# Arm_control_pull.net
KiCad netlist of a schematic drawn in Altium Designer
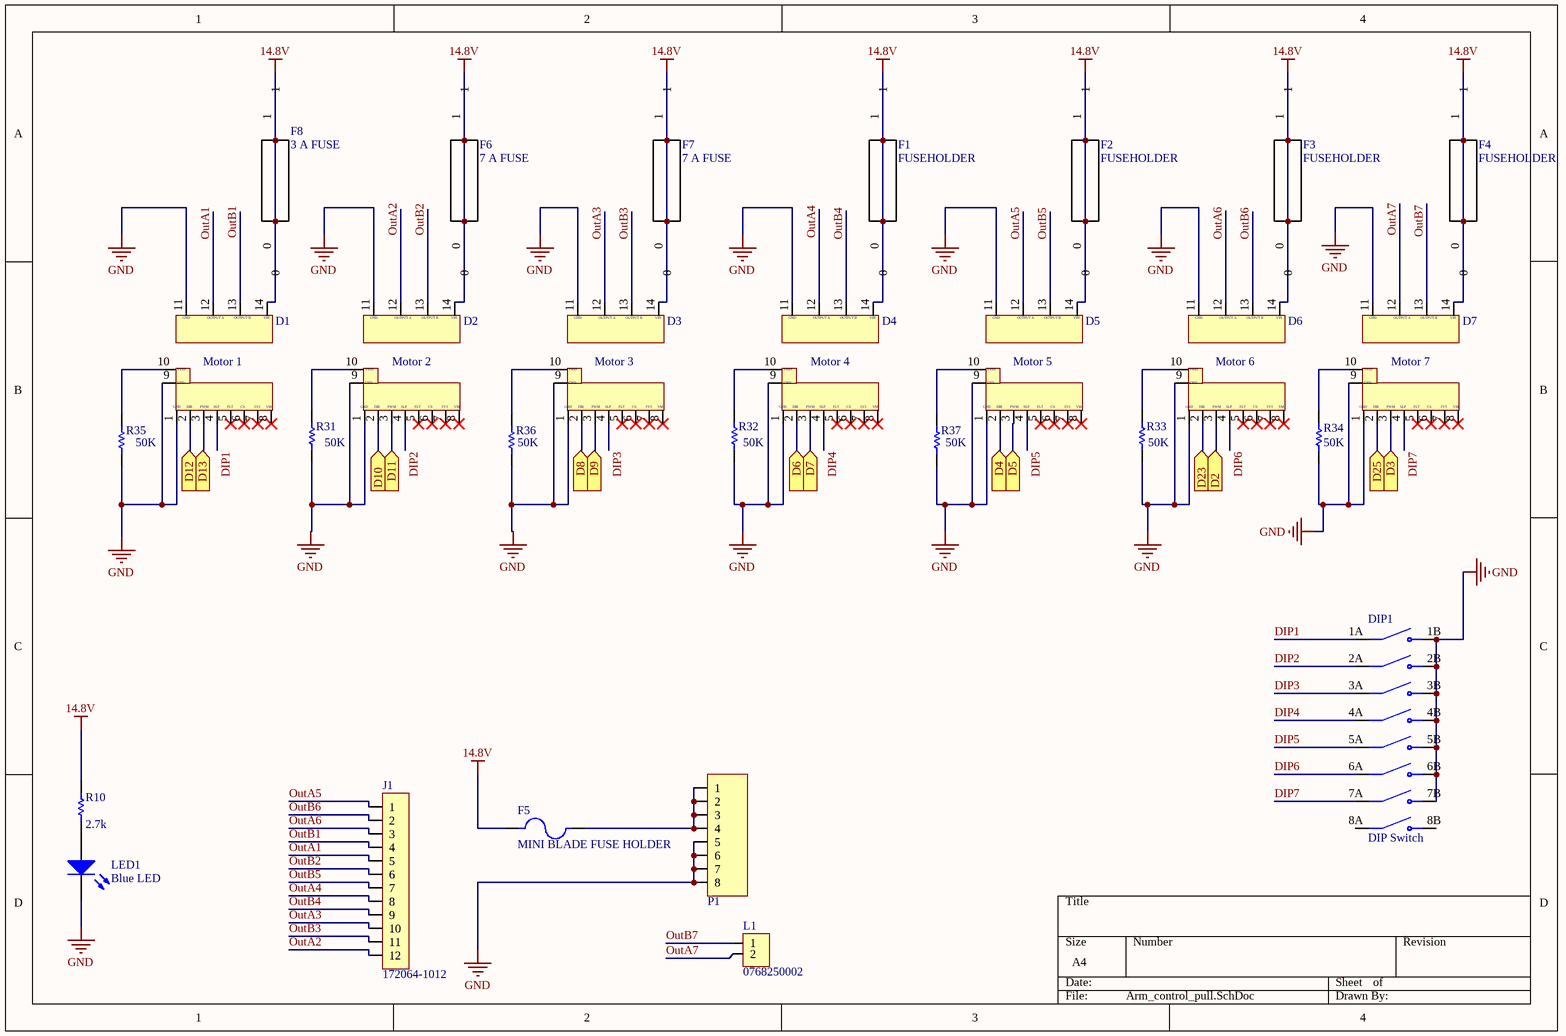
[diagram p0: Arm_control_pull.SchDoc]

(export (version "E")
  (design (tool "Eeschema 10.0.6"))
  (components
    (comp (ref "D1")
      (value "Pololu G2 High-Power Motor Driver 18v25")
      (footprint "POLOLU 18V25")
      (libsource (lib "RSX_Modules") (part "Pololu G2 High-Power Motor Driver 18v25"))
    )
    (comp (ref "D2")
      (value "Pololu G2 High-Power Motor Driver 18v25")
      (footprint "POLOLU 18V25")
      (libsource (lib "RSX_Modules") (part "Pololu G2 High-Power Motor Driver 18v25"))
    )
    (comp (ref "D3")
      (value "Pololu G2 High-Power Motor Driver 18v25")
      (footprint "POLOLU 18V25")
      (libsource (lib "RSX_Modules") (part "Pololu G2 High-Power Motor Driver 18v25"))
    )
    (comp (ref "D4")
      (value "Pololu G2 High-Power Motor Driver 18v25")
      (footprint "POLOLU 18V25")
      (libsource (lib "RSX_Modules") (part "Pololu G2 High-Power Motor Driver 18v25"))
    )
    (comp (ref "D5")
      (value "Pololu G2 High-Power Motor Driver 18v25")
      (footprint "POLOLU 18V25")
      (libsource (lib "RSX_Modules") (part "Pololu G2 High-Power Motor Driver 18v25"))
    )
    (comp (ref "D6")
      (value "Pololu G2 High-Power Motor Driver 18v25")
      (footprint "POLOLU 18V25")
      (libsource (lib "RSX_Modules") (part "Pololu G2 High-Power Motor Driver 18v25"))
    )
    (comp (ref "D7")
      (value "Pololu G2 High-Power Motor Driver 18v25")
      (footprint "POLOLU 18V25")
      (libsource (lib "RSX_Modules") (part "Pololu G2 High-Power Motor Driver 18v25"))
    )
    (comp (ref "DIP1")
      (value "DIP Switch")
      (footprint "DIP Switch")
      (libsource (lib "RSX_Modules") (part "DIP Switch"))
    )
    (comp (ref "F1")
      (value "FUSEHOLDER")
      (footprint "FUSEHOLDER 3557-20")
      (libsource (lib "RSX_Fuses") (part "FUSEHOLDER"))
    )
    (comp (ref "F2")
      (value "FUSEHOLDER")
      (footprint "FUSEHOLDER 3557-20")
      (libsource (lib "RSX_Fuses") (part "FUSEHOLDER"))
    )
    (comp (ref "F3")
      (value "FUSEHOLDER")
      (footprint "FUSEHOLDER 3557-20")
      (libsource (lib "RSX_Fuses") (part "FUSEHOLDER"))
    )
    (comp (ref "F4")
      (value "FUSEHOLDER")
      (footprint "FUSEHOLDER 3557-20")
      (libsource (lib "RSX_Fuses") (part "FUSEHOLDER"))
    )
    (comp (ref "F5")
      (value "MINI BLADE FUSE HOLDER")
      (footprint "RSX_Fuses:MINI FUSE HOLDER")
      (description "Fuse Holder 15A 32V 1 Circuit Blade Through Hole")
      (fields (field (name "MP") "01530007Z"))
      (libsource (lib "RSX_Fuses") (part "01530007Z"))
    )
    (comp (ref "F6")
      (value "7 A FUSE")
      (footprint "7 A FUSE  0407007.WR")
      (libsource (lib "RSX_Fuses") (part "7 A FUSE"))
    )
    (comp (ref "F7")
      (value "7 A FUSE")
      (footprint "7 A FUSE  0407007.WR")
      (libsource (lib "RSX_Fuses") (part "7 A FUSE"))
    )
    (comp (ref "F8")
      (value "3 A FUSE")
      (footprint "3A FUSE ERB-RG3R00V")
      (libsource (lib "RSX_Fuses") (part "3 A FUSE"))
    )
    (comp (ref "J1")
      (value "172064-1012")
      (footprint "172064-1012")
      (description "Conn Shrouded Header HDR 12 POS 5.7mm Solder RA Thru-Hole Tray")
      (libsource (lib "RSX_Connectors") (part "172064-1012"))
    )
    (comp (ref "L1")
      (value "0768250002")
      (footprint "MOLEX 0768250002")
      (description "Conn Power HDR 2 POS 5.7mm Solder RA Thru-Hole 2 Terminal 1 Port")
      (libsource (lib "RSX_Connectors") (part "0768250002"))
    )
    (comp (ref "LED1")
      (value "Blue LED")
      (footprint "LTST-C171TBKT")
      (libsource (lib "RSX_Diodes") (part "Blue LED"))
    )
    (comp (ref "P1")
      (value "Mini-Fit Jr 8 Pos RA")
      (footprint "MOLEX 172065-0208")
      (libsource (lib "RSX_Connectors") (part "Molex Mega-Fit 8pos Vert"))
    )
    (comp (ref "R10")
      (value "2.7k")
      (footprint "RESC1608X06N_0603")
      (description "Resistor")
      (fields (field (name "Comment") "Res1") (field (name "PUBLISHER") "Altium Limited"))
      (libsource (lib "RSX_Resistors") (part "Res1"))
    )
    (comp (ref "R31")
      (value "50K")
      (footprint "RESC1608X06N_0603")
      (description "Resistor")
      (fields (field (name "Comment") "Res1") (field (name "PUBLISHER") "Altium Limited"))
      (libsource (lib "RSX_Resistors") (part "Res1"))
    )
    (comp (ref "R32")
      (value "50K")
      (footprint "RESC1608X06N_0603")
      (description "Resistor")
      (fields (field (name "Comment") "Res1") (field (name "PUBLISHER") "Altium Limited"))
      (libsource (lib "RSX_Resistors") (part "Res1"))
    )
    (comp (ref "R33")
      (value "50K")
      (footprint "RESC1608X06N_0603")
      (description "Resistor")
      (fields (field (name "Comment") "Res1") (field (name "PUBLISHER") "Altium Limited"))
      (libsource (lib "RSX_Resistors") (part "Res1"))
    )
    (comp (ref "R34")
      (value "50K")
      (footprint "RESC1608X06N_0603")
      (description "Resistor")
      (fields (field (name "Comment") "Res1") (field (name "PUBLISHER") "Altium Limited"))
      (libsource (lib "RSX_Resistors") (part "Res1"))
    )
    (comp (ref "R35")
      (value "50K")
      (footprint "RESC1608X06N_0603")
      (description "Resistor")
      (fields (field (name "Comment") "Res1") (field (name "PUBLISHER") "Altium Limited"))
      (libsource (lib "RSX_Resistors") (part "Res1"))
    )
    (comp (ref "R36")
      (value "50K")
      (footprint "RESC1608X06N_0603")
      (description "Resistor")
      (fields (field (name "Comment") "Res1") (field (name "PUBLISHER") "Altium Limited"))
      (libsource (lib "RSX_Resistors") (part "Res1"))
    )
    (comp (ref "R37")
      (value "50K")
      (footprint "RESC1608X06N_0603")
      (description "Resistor")
      (fields (field (name "Comment") "Res1") (field (name "PUBLISHER") "Altium Limited"))
      (libsource (lib "RSX_Resistors") (part "Res1"))
    )
  )
  (nets
    (net (code "2") (name "/D2") (class "Default")
      (node (ref "D6") (pin "3") (pinfunction "3_3") (pintype "passive"))
    )
    (net (code "3") (name "/D3") (class "Default")
      (node (ref "D7") (pin "3") (pinfunction "3_3") (pintype "passive"))
    )
    (net (code "4") (name "/D4") (class "Default")
      (node (ref "D5") (pin "2") (pinfunction "2_2") (pintype "passive"))
    )
    (net (code "5") (name "/D5") (class "Default")
      (node (ref "D5") (pin "3") (pinfunction "3_3") (pintype "passive"))
    )
    (net (code "6") (name "/D6") (class "Default")
      (node (ref "D4") (pin "2") (pinfunction "2_2") (pintype "passive"))
    )
    (net (code "7") (name "/D7") (class "Default")
      (node (ref "D4") (pin "3") (pinfunction "3_3") (pintype "passive"))
    )
    (net (code "8") (name "/D8") (class "Default")
      (node (ref "D3") (pin "2") (pinfunction "2_2") (pintype "passive"))
    )
    (net (code "9") (name "/D9") (class "Default")
      (node (ref "D3") (pin "3") (pinfunction "3_3") (pintype "passive"))
    )
    (net (code "10") (name "/D10") (class "Default")
      (node (ref "D2") (pin "2") (pinfunction "2_2") (pintype "passive"))
    )
    (net (code "11") (name "/D11") (class "Default")
      (node (ref "D2") (pin "3") (pinfunction "3_3") (pintype "passive"))
    )
    (net (code "12") (name "/D12") (class "Default")
      (node (ref "D1") (pin "2") (pinfunction "2_2") (pintype "passive"))
    )
    (net (code "13") (name "/D13") (class "Default")
      (node (ref "D1") (pin "3") (pinfunction "3_3") (pintype "passive"))
    )
    (net (code "14") (name "/D23") (class "Default")
      (node (ref "D6") (pin "2") (pinfunction "2_2") (pintype "passive"))
    )
    (net (code "15") (name "/D25") (class "Default")
      (node (ref "D7") (pin "2") (pinfunction "2_2") (pintype "passive"))
    )
    (net (code "16") (name "/DIP1") (class "Default")
      (node (ref "D1") (pin "4") (pinfunction "4_4") (pintype "passive"))
      (node (ref "DIP1") (pin "1A") (pinfunction "COM1_1A") (pintype "passive"))
    )
    (net (code "17") (name "/DIP2") (class "Default")
      (node (ref "D2") (pin "4") (pinfunction "4_4") (pintype "passive"))
      (node (ref "DIP1") (pin "2A") (pinfunction "COM2_2A") (pintype "passive"))
    )
    (net (code "18") (name "/DIP3") (class "Default")
      (node (ref "D3") (pin "4") (pinfunction "4_4") (pintype "passive"))
      (node (ref "DIP1") (pin "3A") (pinfunction "COM3_3A") (pintype "passive"))
    )
    (net (code "19") (name "/DIP4") (class "Default")
      (node (ref "D4") (pin "4") (pinfunction "4_4") (pintype "passive"))
      (node (ref "DIP1") (pin "4A") (pinfunction "COM4_4A") (pintype "passive"))
    )
    (net (code "20") (name "/DIP5") (class "Default")
      (node (ref "D5") (pin "4") (pinfunction "4_4") (pintype "passive"))
      (node (ref "DIP1") (pin "5A") (pinfunction "COM5_5A") (pintype "passive"))
    )
    (net (code "21") (name "/DIP6") (class "Default")
      (node (ref "D6") (pin "4") (pinfunction "4_4") (pintype "passive"))
      (node (ref "DIP1") (pin "6A") (pinfunction "COM6_6A") (pintype "passive"))
    )
    (net (code "22") (name "/DIP7") (class "Default")
      (node (ref "D7") (pin "4") (pinfunction "4_4") (pintype "passive"))
      (node (ref "DIP1") (pin "7A") (pinfunction "COM7_7A") (pintype "passive"))
    )
    (net (code "23") (name "/OutA1") (class "Default")
      (node (ref "D1") (pin "12") (pinfunction "12_12") (pintype "passive"))
      (node (ref "J1") (pin "5") (pinfunction "5_5") (pintype "passive"))
    )
    (net (code "24") (name "/OutA2") (class "Default")
      (node (ref "D2") (pin "12") (pinfunction "12_12") (pintype "passive"))
      (node (ref "J1") (pin "12") (pinfunction "12_12") (pintype "passive"))
    )
    (net (code "25") (name "/OutA3") (class "Default")
      (node (ref "D3") (pin "12") (pinfunction "12_12") (pintype "passive"))
      (node (ref "J1") (pin "10") (pinfunction "10_10") (pintype "passive"))
    )
    (net (code "26") (name "/OutA4") (class "Default")
      (node (ref "D4") (pin "12") (pinfunction "12_12") (pintype "passive"))
      (node (ref "J1") (pin "8") (pinfunction "8_8") (pintype "passive"))
    )
    (net (code "27") (name "/OutA5") (class "Default")
      (node (ref "D5") (pin "12") (pinfunction "12_12") (pintype "passive"))
      (node (ref "J1") (pin "1") (pinfunction "1_1") (pintype "passive"))
    )
    (net (code "28") (name "/OutA6") (class "Default")
      (node (ref "D6") (pin "12") (pinfunction "12_12") (pintype "passive"))
      (node (ref "J1") (pin "3") (pinfunction "3_3") (pintype "passive"))
    )
    (net (code "29") (name "/OutA7") (class "Default")
      (node (ref "D7") (pin "12") (pinfunction "12_12") (pintype "passive"))
      (node (ref "L1") (pin "2") (pinfunction "2_2") (pintype "passive"))
    )
    (net (code "30") (name "/OutB1") (class "Default")
      (node (ref "D1") (pin "13") (pinfunction "13_13") (pintype "passive"))
      (node (ref "J1") (pin "4") (pinfunction "4_4") (pintype "passive"))
    )
    (net (code "31") (name "/OutB2") (class "Default")
      (node (ref "D2") (pin "13") (pinfunction "13_13") (pintype "passive"))
      (node (ref "J1") (pin "6") (pinfunction "6_6") (pintype "passive"))
    )
    (net (code "32") (name "/OutB3") (class "Default")
      (node (ref "D3") (pin "13") (pinfunction "13_13") (pintype "passive"))
      (node (ref "J1") (pin "11") (pinfunction "11_11") (pintype "passive"))
    )
    (net (code "33") (name "/OutB4") (class "Default")
      (node (ref "D4") (pin "13") (pinfunction "13_13") (pintype "passive"))
      (node (ref "J1") (pin "9") (pinfunction "9_9") (pintype "passive"))
    )
    (net (code "34") (name "/OutB5") (class "Default")
      (node (ref "D5") (pin "13") (pinfunction "13_13") (pintype "passive"))
      (node (ref "J1") (pin "7") (pinfunction "7_7") (pintype "passive"))
    )
    (net (code "35") (name "/OutB6") (class "Default")
      (node (ref "D6") (pin "13") (pinfunction "13_13") (pintype "passive"))
      (node (ref "J1") (pin "2") (pinfunction "2_2") (pintype "passive"))
    )
    (net (code "36") (name "/OutB7") (class "Default")
      (node (ref "D7") (pin "13") (pinfunction "13_13") (pintype "passive"))
      (node (ref "L1") (pin "1") (pinfunction "1_1") (pintype "passive"))
    )
    (net (code "37") (name "14.8V") (class "Default")
      (node (ref "D1") (pin "14") (pinfunction "14_14") (pintype "passive"))
      (node (ref "D2") (pin "14") (pinfunction "14_14") (pintype "passive"))
      (node (ref "D3") (pin "14") (pinfunction "14_14") (pintype "passive"))
      (node (ref "D4") (pin "14") (pinfunction "14_14") (pintype "passive"))
      (node (ref "D5") (pin "14") (pinfunction "14_14") (pintype "passive"))
      (node (ref "D6") (pin "14") (pinfunction "14_14") (pintype "passive"))
      (node (ref "D7") (pin "14") (pinfunction "14_14") (pintype "passive"))
      (node (ref "F1") (pin "0") (pinfunction "0_0") (pintype "passive"))
      (node (ref "F1") (pin "1") (pinfunction "1_1") (pintype "passive"))
      (node (ref "F2") (pin "0") (pinfunction "0_0") (pintype "passive"))
      (node (ref "F2") (pin "1") (pinfunction "1_1") (pintype "passive"))
      (node (ref "F3") (pin "0") (pinfunction "0_0") (pintype "passive"))
      (node (ref "F3") (pin "1") (pinfunction "1_1") (pintype "passive"))
      (node (ref "F4") (pin "0") (pinfunction "0_0") (pintype "passive"))
      (node (ref "F4") (pin "1") (pinfunction "1_1") (pintype "passive"))
      (node (ref "F5") (pin "2") (pinfunction "2_2") (pintype "passive"))
      (node (ref "F6") (pin "0") (pinfunction "0_0") (pintype "passive"))
      (node (ref "F6") (pin "1") (pinfunction "1_1") (pintype "passive"))
      (node (ref "F7") (pin "0") (pinfunction "0_0") (pintype "passive"))
      (node (ref "F7") (pin "1") (pinfunction "1_1") (pintype "passive"))
      (node (ref "F8") (pin "0") (pinfunction "0_0") (pintype "passive"))
      (node (ref "F8") (pin "1") (pinfunction "1_1") (pintype "passive"))
      (node (ref "R10") (pin "1") (pinfunction "1_1") (pintype "passive"))
    )
    (net (code "38") (name "GND") (class "Default")
      (node (ref "D1") (pin "1") (pinfunction "1_1") (pintype "passive"))
      (node (ref "D1") (pin "11") (pinfunction "11_11") (pintype "passive"))
      (node (ref "D1") (pin "9") (pinfunction "9_9") (pintype "passive"))
      (node (ref "D2") (pin "1") (pinfunction "1_1") (pintype "passive"))
      (node (ref "D2") (pin "11") (pinfunction "11_11") (pintype "passive"))
      (node (ref "D2") (pin "9") (pinfunction "9_9") (pintype "passive"))
      (node (ref "D3") (pin "1") (pinfunction "1_1") (pintype "passive"))
      (node (ref "D3") (pin "11") (pinfunction "11_11") (pintype "passive"))
      (node (ref "D3") (pin "9") (pinfunction "9_9") (pintype "passive"))
      (node (ref "D4") (pin "1") (pinfunction "1_1") (pintype "passive"))
      (node (ref "D4") (pin "11") (pinfunction "11_11") (pintype "passive"))
      (node (ref "D4") (pin "9") (pinfunction "9_9") (pintype "passive"))
      (node (ref "D5") (pin "1") (pinfunction "1_1") (pintype "passive"))
      (node (ref "D5") (pin "11") (pinfunction "11_11") (pintype "passive"))
      (node (ref "D5") (pin "9") (pinfunction "9_9") (pintype "passive"))
      (node (ref "D6") (pin "1") (pinfunction "1_1") (pintype "passive"))
      (node (ref "D6") (pin "11") (pinfunction "11_11") (pintype "passive"))
      (node (ref "D6") (pin "9") (pinfunction "9_9") (pintype "passive"))
      (node (ref "D7") (pin "1") (pinfunction "1_1") (pintype "passive"))
      (node (ref "D7") (pin "11") (pinfunction "11_11") (pintype "passive"))
      (node (ref "D7") (pin "9") (pinfunction "9_9") (pintype "passive"))
      (node (ref "DIP1") (pin "1B") (pinfunction "NO1_1B") (pintype "passive"))
      (node (ref "DIP1") (pin "2B") (pinfunction "NO2_2B") (pintype "passive"))
      (node (ref "DIP1") (pin "3B") (pinfunction "NO3_3B") (pintype "passive"))
      (node (ref "DIP1") (pin "4B") (pinfunction "NO4_4B") (pintype "passive"))
      (node (ref "DIP1") (pin "5B") (pinfunction "NO5_5B") (pintype "passive"))
      (node (ref "DIP1") (pin "6B") (pinfunction "NO6_6B") (pintype "passive"))
      (node (ref "DIP1") (pin "7B") (pinfunction "NO7_7B") (pintype "passive"))
      (node (ref "LED1") (pin "2") (pinfunction "K_2") (pintype "passive"))
      (node (ref "P1") (pin "5") (pinfunction "5_5") (pintype "passive"))
      (node (ref "P1") (pin "6") (pinfunction "6_6") (pintype "passive"))
      (node (ref "P1") (pin "7") (pinfunction "7_7") (pintype "passive"))
      (node (ref "P1") (pin "8") (pinfunction "8_8") (pintype "passive"))
      (node (ref "R31") (pin "1") (pinfunction "1_1") (pintype "passive"))
      (node (ref "R32") (pin "1") (pinfunction "1_1") (pintype "passive"))
      (node (ref "R33") (pin "1") (pinfunction "1_1") (pintype "passive"))
      (node (ref "R34") (pin "1") (pinfunction "1_1") (pintype "passive"))
      (node (ref "R35") (pin "1") (pinfunction "1_1") (pintype "passive"))
      (node (ref "R36") (pin "1") (pinfunction "1_1") (pintype "passive"))
      (node (ref "R37") (pin "1") (pinfunction "1_1") (pintype "passive"))
    )
    (net (code "39") (name "Net-(D1-Pad10)") (class "Default")
      (node (ref "D1") (pin "10") (pinfunction "10_10") (pintype "passive"))
      (node (ref "R35") (pin "2") (pinfunction "2_2") (pintype "passive"))
    )
    (net (code "40") (name "Net-(D2-Pad10)") (class "Default")
      (node (ref "D2") (pin "10") (pinfunction "10_10") (pintype "passive"))
      (node (ref "R31") (pin "2") (pinfunction "2_2") (pintype "passive"))
    )
    (net (code "41") (name "Net-(D3-Pad10)") (class "Default")
      (node (ref "D3") (pin "10") (pinfunction "10_10") (pintype "passive"))
      (node (ref "R36") (pin "2") (pinfunction "2_2") (pintype "passive"))
    )
    (net (code "42") (name "Net-(D4-Pad10)") (class "Default")
      (node (ref "D4") (pin "10") (pinfunction "10_10") (pintype "passive"))
      (node (ref "R32") (pin "2") (pinfunction "2_2") (pintype "passive"))
    )
    (net (code "43") (name "Net-(D5-Pad10)") (class "Default")
      (node (ref "D5") (pin "10") (pinfunction "10_10") (pintype "passive"))
      (node (ref "R37") (pin "2") (pinfunction "2_2") (pintype "passive"))
    )
    (net (code "44") (name "Net-(D6-Pad10)") (class "Default")
      (node (ref "D6") (pin "10") (pinfunction "10_10") (pintype "passive"))
      (node (ref "R33") (pin "2") (pinfunction "2_2") (pintype "passive"))
    )
    (net (code "45") (name "Net-(D7-Pad10)") (class "Default")
      (node (ref "D7") (pin "10") (pinfunction "10_10") (pintype "passive"))
      (node (ref "R34") (pin "2") (pinfunction "2_2") (pintype "passive"))
    )
    (net (code "46") (name "Net-(F5-Pad1)") (class "Default")
      (node (ref "F5") (pin "1") (pinfunction "1_1") (pintype "passive"))
      (node (ref "P1") (pin "1") (pinfunction "1_1") (pintype "passive"))
      (node (ref "P1") (pin "2") (pinfunction "2_2") (pintype "passive"))
      (node (ref "P1") (pin "3") (pinfunction "3_3") (pintype "passive"))
      (node (ref "P1") (pin "4") (pinfunction "4_4") (pintype "passive"))
    )
    (net (code "47") (name "Net-(LED1-A)") (class "Default")
      (node (ref "LED1") (pin "1") (pinfunction "A_1") (pintype "passive"))
      (node (ref "R10") (pin "2") (pinfunction "2_2") (pintype "passive"))
    )
    (net (code "48") (name "unconnected-(D1-Pad5)") (class "Default")
      (node (ref "D1") (pin "5") (pinfunction "5_5") (pintype "passive+no_connect"))
    )
    (net (code "49") (name "unconnected-(D1-Pad6)") (class "Default")
      (node (ref "D1") (pin "6") (pinfunction "6_6") (pintype "passive+no_connect"))
    )
    (net (code "50") (name "unconnected-(D1-Pad7)") (class "Default")
      (node (ref "D1") (pin "7") (pinfunction "7_7") (pintype "passive+no_connect"))
    )
    (net (code "51") (name "unconnected-(D1-Pad8)") (class "Default")
      (node (ref "D1") (pin "8") (pinfunction "8_8") (pintype "passive+no_connect"))
    )
    (net (code "52") (name "unconnected-(D2-Pad5)") (class "Default")
      (node (ref "D2") (pin "5") (pinfunction "5_5") (pintype "passive+no_connect"))
    )
    (net (code "53") (name "unconnected-(D2-Pad6)") (class "Default")
      (node (ref "D2") (pin "6") (pinfunction "6_6") (pintype "passive+no_connect"))
    )
    (net (code "54") (name "unconnected-(D2-Pad7)") (class "Default")
      (node (ref "D2") (pin "7") (pinfunction "7_7") (pintype "passive+no_connect"))
    )
    (net (code "55") (name "unconnected-(D2-Pad8)") (class "Default")
      (node (ref "D2") (pin "8") (pinfunction "8_8") (pintype "passive+no_connect"))
    )
    (net (code "56") (name "unconnected-(D3-Pad5)") (class "Default")
      (node (ref "D3") (pin "5") (pinfunction "5_5") (pintype "passive+no_connect"))
    )
    (net (code "57") (name "unconnected-(D3-Pad6)") (class "Default")
      (node (ref "D3") (pin "6") (pinfunction "6_6") (pintype "passive+no_connect"))
    )
    (net (code "58") (name "unconnected-(D3-Pad7)") (class "Default")
      (node (ref "D3") (pin "7") (pinfunction "7_7") (pintype "passive+no_connect"))
    )
    (net (code "59") (name "unconnected-(D3-Pad8)") (class "Default")
      (node (ref "D3") (pin "8") (pinfunction "8_8") (pintype "passive+no_connect"))
    )
    (net (code "60") (name "unconnected-(D4-Pad5)") (class "Default")
      (node (ref "D4") (pin "5") (pinfunction "5_5") (pintype "passive+no_connect"))
    )
    (net (code "61") (name "unconnected-(D4-Pad6)") (class "Default")
      (node (ref "D4") (pin "6") (pinfunction "6_6") (pintype "passive+no_connect"))
    )
    (net (code "62") (name "unconnected-(D4-Pad7)") (class "Default")
      (node (ref "D4") (pin "7") (pinfunction "7_7") (pintype "passive+no_connect"))
    )
    (net (code "63") (name "unconnected-(D4-Pad8)") (class "Default")
      (node (ref "D4") (pin "8") (pinfunction "8_8") (pintype "passive+no_connect"))
    )
    (net (code "64") (name "unconnected-(D5-Pad5)") (class "Default")
      (node (ref "D5") (pin "5") (pinfunction "5_5") (pintype "passive+no_connect"))
    )
    (net (code "65") (name "unconnected-(D5-Pad6)") (class "Default")
      (node (ref "D5") (pin "6") (pinfunction "6_6") (pintype "passive+no_connect"))
    )
    (net (code "66") (name "unconnected-(D5-Pad7)") (class "Default")
      (node (ref "D5") (pin "7") (pinfunction "7_7") (pintype "passive+no_connect"))
    )
    (net (code "67") (name "unconnected-(D5-Pad8)") (class "Default")
      (node (ref "D5") (pin "8") (pinfunction "8_8") (pintype "passive+no_connect"))
    )
    (net (code "68") (name "unconnected-(D6-Pad5)") (class "Default")
      (node (ref "D6") (pin "5") (pinfunction "5_5") (pintype "passive+no_connect"))
    )
    (net (code "69") (name "unconnected-(D6-Pad6)") (class "Default")
      (node (ref "D6") (pin "6") (pinfunction "6_6") (pintype "passive+no_connect"))
    )
    (net (code "70") (name "unconnected-(D6-Pad7)") (class "Default")
      (node (ref "D6") (pin "7") (pinfunction "7_7") (pintype "passive+no_connect"))
    )
    (net (code "71") (name "unconnected-(D6-Pad8)") (class "Default")
      (node (ref "D6") (pin "8") (pinfunction "8_8") (pintype "passive+no_connect"))
    )
    (net (code "72") (name "unconnected-(D7-Pad5)") (class "Default")
      (node (ref "D7") (pin "5") (pinfunction "5_5") (pintype "passive+no_connect"))
    )
    (net (code "73") (name "unconnected-(D7-Pad6)") (class "Default")
      (node (ref "D7") (pin "6") (pinfunction "6_6") (pintype "passive+no_connect"))
    )
    (net (code "74") (name "unconnected-(D7-Pad7)") (class "Default")
      (node (ref "D7") (pin "7") (pinfunction "7_7") (pintype "passive+no_connect"))
    )
    (net (code "75") (name "unconnected-(D7-Pad8)") (class "Default")
      (node (ref "D7") (pin "8") (pinfunction "8_8") (pintype "passive+no_connect"))
    )
    (net (code "76") (name "unconnected-(DIP1-COM8-Pad8A)") (class "Default")
      (node (ref "DIP1") (pin "8A") (pinfunction "COM8_8A") (pintype "passive"))
    )
    (net (code "77") (name "unconnected-(DIP1-NO8-Pad8B)") (class "Default")
      (node (ref "DIP1") (pin "8B") (pinfunction "NO8_8B") (pintype "passive"))
    )
  )
)
